# PowerAndUSB.net
KiCad netlist of a schematic drawn in Altium Designer
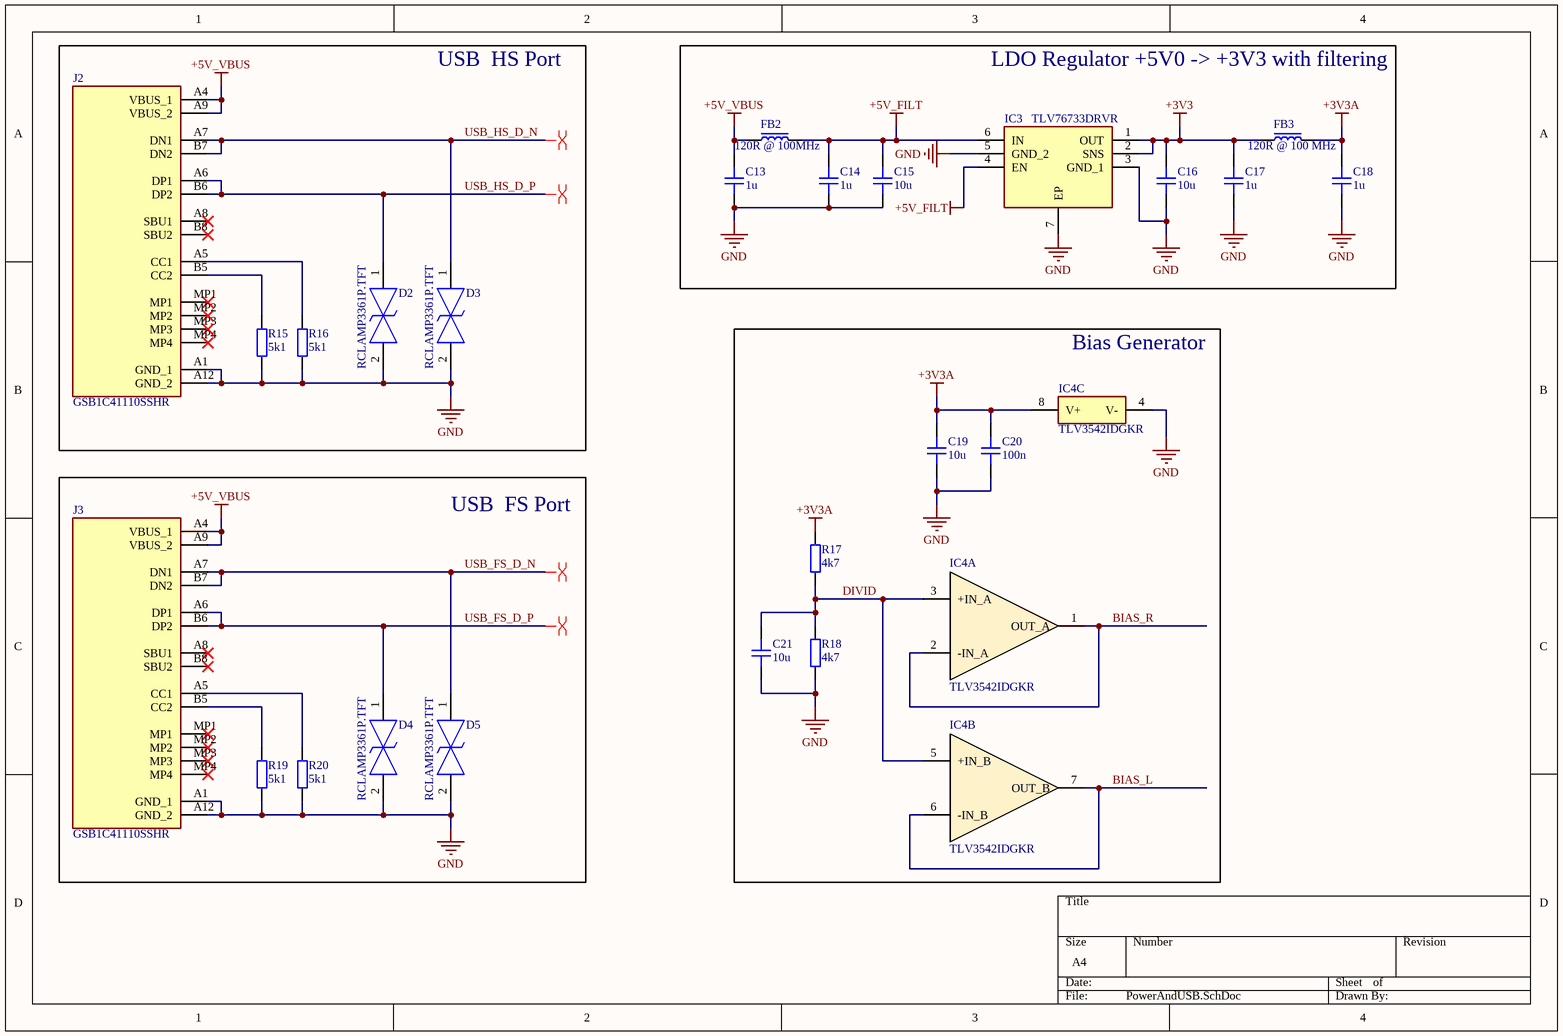
[diagram p0: PowerAndUSB.SchDoc]

(export (version "E")
  (design (tool "Eeschema 10.0.6"))
  (components
    (comp (ref "C13")
      (value "1u")
      (footprint "CAP_0805")
      (description "Capacitor SMD 0805")
      (libsource (lib "Schematic-Lib-PhilsLab") (part "CAP_0805"))
    )
    (comp (ref "C14")
      (value "1u")
      (footprint "CAP_0805")
      (description "Capacitor SMD 0805")
      (libsource (lib "Schematic-Lib-PhilsLab") (part "CAP_0805"))
    )
    (comp (ref "C15")
      (value "10u")
      (footprint "CAP_0805")
      (description "Capacitor SMD 0805")
      (libsource (lib "Schematic-Lib-PhilsLab") (part "CAP_0805"))
    )
    (comp (ref "C16")
      (value "10u")
      (footprint "CAP_0805")
      (description "Capacitor SMD 0805")
      (libsource (lib "Schematic-Lib-PhilsLab") (part "CAP_0805"))
    )
    (comp (ref "C17")
      (value "1u")
      (footprint "CAP_0402")
      (description "Capacitor SMD 0402")
      (libsource (lib "Schematic-Lib-PhilsLab") (part "CAP_0402"))
    )
    (comp (ref "C18")
      (value "1u")
      (footprint "CAP_0402")
      (description "Capacitor SMD 0402")
      (libsource (lib "Schematic-Lib-PhilsLab") (part "CAP_0402"))
    )
    (comp (ref "C19")
      (value "10u")
      (footprint "CAP_0603")
      (description "Capacitor SMD 0603")
      (libsource (lib "Schematic-Lib-PhilsLab") (part "CAP_0603"))
    )
    (comp (ref "C20")
      (value "100n")
      (footprint "CAP_0402")
      (description "Capacitor SMD 0402")
      (libsource (lib "Schematic-Lib-PhilsLab") (part "CAP_0402"))
    )
    (comp (ref "C21")
      (value "10u")
      (footprint "CAP_0603")
      (description "Capacitor SMD 0603")
      (libsource (lib "Schematic-Lib-PhilsLab") (part "CAP_0603"))
    )
    (comp (ref "D2")
      (value "RCLAMP3361P.TFT")
      (footprint "BAT_Detector_PCBLib:RCLAMP3361PTFT")
      (description "TVS Diode (Bi-directional)")
      (libsource (lib "BAT_Detector_SCHLib") (part "RCLAMP3361P.TFT"))
    )
    (comp (ref "D3")
      (value "RCLAMP3361P.TFT")
      (footprint "BAT_Detector_PCBLib:RCLAMP3361PTFT")
      (description "TVS Diode (Bi-directional)")
      (libsource (lib "BAT_Detector_SCHLib") (part "RCLAMP3361P.TFT"))
    )
    (comp (ref "D4")
      (value "RCLAMP3361P.TFT")
      (footprint "BAT_Detector_PCBLib:RCLAMP3361PTFT")
      (description "TVS Diode (Bi-directional)")
      (libsource (lib "BAT_Detector_SCHLib") (part "RCLAMP3361P.TFT"))
    )
    (comp (ref "D5")
      (value "RCLAMP3361P.TFT")
      (footprint "BAT_Detector_PCBLib:RCLAMP3361PTFT")
      (description "TVS Diode (Bi-directional)")
      (libsource (lib "BAT_Detector_SCHLib") (part "RCLAMP3361P.TFT"))
    )
    (comp (ref "FB2")
      (value "120R @ 100MHz")
      (footprint "FB_0805")
      (description "Ferrite Bead SMD 0805")
      (libsource (lib "Schematic-Lib-PhilsLab") (part "FB_0805"))
    )
    (comp (ref "FB3")
      (value "120R @ 100 MHz")
      (footprint "FB_0603")
      (description "Ferrite Bead SMD 0603")
      (libsource (lib "Schematic-Lib-PhilsLab") (part "FB_0603"))
    )
    (comp (ref "IC3")
      (value "TLV76733DRVR")
      (footprint "BAT_Detector_PCBLib:SON65P200X200X80-7N")
      (description "Integrated Circuit")
      (fields (field (name "MOUSER PART NUMBER") "595-TLV76733DRVR"))
      (libsource (lib "BAT_Detector_SCHLib") (part "TLV76733DRVR"))
    )
    (comp (ref "IC4")
      (value "TLV3542IDGKR")
      (footprint "BAT_Detector_PCBLib:SOP65P490X110-8N")
      (description "Integrated Circuit")
      (fields (field (name "MOUSER PART NUMBER") "595-TLV3542IDGKR"))
      (libsource (lib "BAT_Detector_SCHLib") (part "TLV3542IDGKR"))
    )
    (comp (ref "J2")
      (value "GSB1C41110SSHR")
      (footprint "BAT_Detector_PCBLib:GSB1C41110SSHR")
      (description "Connector")
      (libsource (lib "BAT_Detector_SCHLib") (part "GSB1C41110SSHR"))
    )
    (comp (ref "J3")
      (value "GSB1C41110SSHR")
      (footprint "BAT_Detector_PCBLib:GSB1C41110SSHR")
      (description "Connector")
      (libsource (lib "BAT_Detector_SCHLib") (part "GSB1C41110SSHR"))
    )
    (comp (ref "R15")
      (value "5k1")
      (footprint "RES_0402")
      (description "Resistor SMD 0402")
      (libsource (lib "Schematic-Lib-PhilsLab") (part "RES_0402"))
    )
    (comp (ref "R16")
      (value "5k1")
      (footprint "RES_0402")
      (description "Resistor SMD 0402")
      (libsource (lib "Schematic-Lib-PhilsLab") (part "RES_0402"))
    )
    (comp (ref "R17")
      (value "4k7")
      (footprint "RES_0603")
      (description "Resistor SMD 0603")
      (libsource (lib "Schematic-Lib-PhilsLab") (part "RES_0603"))
    )
    (comp (ref "R18")
      (value "4k7")
      (footprint "RES_0603")
      (description "Resistor SMD 0603")
      (libsource (lib "Schematic-Lib-PhilsLab") (part "RES_0603"))
    )
    (comp (ref "R19")
      (value "5k1")
      (footprint "RES_0402")
      (description "Resistor SMD 0402")
      (libsource (lib "Schematic-Lib-PhilsLab") (part "RES_0402"))
    )
    (comp (ref "R20")
      (value "5k1")
      (footprint "RES_0402")
      (description "Resistor SMD 0402")
      (libsource (lib "Schematic-Lib-PhilsLab") (part "RES_0402"))
    )
  )
  (nets
    (net (code "1") (name "+3V3") (class "Default")
      (node (ref "C16") (pin "2") (pinfunction "2_2") (pintype "passive"))
      (node (ref "C17") (pin "1") (pinfunction "1_1") (pintype "passive"))
      (node (ref "FB3") (pin "1") (pinfunction "1_1") (pintype "passive"))
      (node (ref "IC3") (pin "1") (pinfunction "OUT_1") (pintype "passive"))
      (node (ref "IC3") (pin "2") (pinfunction "SNS_2") (pintype "passive"))
    )
    (net (code "2") (name "+3V3A") (class "Default")
      (node (ref "C18") (pin "1") (pinfunction "1_1") (pintype "passive"))
      (node (ref "C19") (pin "2") (pinfunction "2_2") (pintype "passive"))
      (node (ref "C20") (pin "2") (pinfunction "2_2") (pintype "passive"))
      (node (ref "FB3") (pin "2") (pinfunction "2_2") (pintype "passive"))
      (node (ref "IC4") (pin "8") (pinfunction "V+_8") (pintype "passive"))
      (node (ref "R17") (pin "2") (pinfunction "2_2") (pintype "passive"))
    )
    (net (code "3") (name "+5V_FILT") (class "Default")
      (node (ref "C14") (pin "2") (pinfunction "2_2") (pintype "passive"))
      (node (ref "C15") (pin "2") (pinfunction "2_2") (pintype "passive"))
      (node (ref "FB2") (pin "2") (pinfunction "2_2") (pintype "passive"))
      (node (ref "IC3") (pin "4") (pinfunction "EN_4") (pintype "passive"))
      (node (ref "IC3") (pin "6") (pinfunction "IN_6") (pintype "passive"))
    )
    (net (code "4") (name "+5V_VBUS") (class "Default")
      (node (ref "C13") (pin "2") (pinfunction "2_2") (pintype "passive"))
      (node (ref "FB2") (pin "1") (pinfunction "1_1") (pintype "passive"))
      (node (ref "J2") (pin "A4") (pinfunction "VBUS_1_A4") (pintype "passive"))
      (node (ref "J2") (pin "A9") (pinfunction "VBUS_2_A9") (pintype "passive"))
      (node (ref "J3") (pin "A4") (pinfunction "VBUS_1_A4") (pintype "passive"))
      (node (ref "J3") (pin "A9") (pinfunction "VBUS_2_A9") (pintype "passive"))
    )
    (net (code "5") (name "/BIAS_L") (class "Default")
      (node (ref "IC4") (pin "6") (pinfunction "-IN_B_6") (pintype "passive"))
      (node (ref "IC4") (pin "7") (pinfunction "OUT_B_7") (pintype "passive"))
    )
    (net (code "6") (name "/BIAS_R") (class "Default")
      (node (ref "IC4") (pin "1") (pinfunction "OUT_A_1") (pintype "passive"))
      (node (ref "IC4") (pin "2") (pinfunction "-IN_A_2") (pintype "passive"))
    )
    (net (code "7") (name "/DIVID") (class "Default")
      (node (ref "C21") (pin "2") (pinfunction "2_2") (pintype "passive"))
      (node (ref "IC4") (pin "3") (pinfunction "+IN_A_3") (pintype "passive"))
      (node (ref "IC4") (pin "5") (pinfunction "+IN_B_5") (pintype "passive"))
      (node (ref "R17") (pin "1") (pinfunction "1_1") (pintype "passive"))
      (node (ref "R18") (pin "2") (pinfunction "2_2") (pintype "passive"))
    )
    (net (code "8") (name "/USB_FS_D_N") (class "Default")
      (node (ref "D5") (pin "1") (pinfunction "1_1") (pintype "passive"))
      (node (ref "J3") (pin "A7") (pinfunction "DN1_A7") (pintype "passive"))
      (node (ref "J3") (pin "B7") (pinfunction "DN2_B7") (pintype "passive"))
    )
    (net (code "9") (name "/USB_FS_D_P") (class "Default")
      (node (ref "D4") (pin "1") (pinfunction "1_1") (pintype "passive"))
      (node (ref "J3") (pin "A6") (pinfunction "DP1_A6") (pintype "passive"))
      (node (ref "J3") (pin "B6") (pinfunction "DP2_B6") (pintype "passive"))
    )
    (net (code "10") (name "/USB_HS_D_N") (class "Default")
      (node (ref "D3") (pin "1") (pinfunction "1_1") (pintype "passive"))
      (node (ref "J2") (pin "A7") (pinfunction "DN1_A7") (pintype "passive"))
      (node (ref "J2") (pin "B7") (pinfunction "DN2_B7") (pintype "passive"))
    )
    (net (code "11") (name "/USB_HS_D_P") (class "Default")
      (node (ref "D2") (pin "1") (pinfunction "1_1") (pintype "passive"))
      (node (ref "J2") (pin "A6") (pinfunction "DP1_A6") (pintype "passive"))
      (node (ref "J2") (pin "B6") (pinfunction "DP2_B6") (pintype "passive"))
    )
    (net (code "12") (name "GND") (class "Default")
      (node (ref "C13") (pin "1") (pinfunction "1_1") (pintype "passive"))
      (node (ref "C14") (pin "1") (pinfunction "1_1") (pintype "passive"))
      (node (ref "C15") (pin "1") (pinfunction "1_1") (pintype "passive"))
      (node (ref "C16") (pin "1") (pinfunction "1_1") (pintype "passive"))
      (node (ref "C17") (pin "2") (pinfunction "2_2") (pintype "passive"))
      (node (ref "C18") (pin "2") (pinfunction "2_2") (pintype "passive"))
      (node (ref "C19") (pin "1") (pinfunction "1_1") (pintype "passive"))
      (node (ref "C20") (pin "1") (pinfunction "1_1") (pintype "passive"))
      (node (ref "C21") (pin "1") (pinfunction "1_1") (pintype "passive"))
      (node (ref "D2") (pin "2") (pinfunction "2_2") (pintype "passive"))
      (node (ref "D3") (pin "2") (pinfunction "2_2") (pintype "passive"))
      (node (ref "D4") (pin "2") (pinfunction "2_2") (pintype "passive"))
      (node (ref "D5") (pin "2") (pinfunction "2_2") (pintype "passive"))
      (node (ref "IC3") (pin "3") (pinfunction "GND_1_3") (pintype "passive"))
      (node (ref "IC3") (pin "5") (pinfunction "GND_2_5") (pintype "passive"))
      (node (ref "IC3") (pin "7") (pinfunction "EP_7") (pintype "passive"))
      (node (ref "IC4") (pin "4") (pinfunction "V-_4") (pintype "passive"))
      (node (ref "J2") (pin "A1") (pinfunction "GND_1_A1") (pintype "passive"))
      (node (ref "J2") (pin "A12") (pinfunction "GND_2_A12") (pintype "passive"))
      (node (ref "J3") (pin "A1") (pinfunction "GND_1_A1") (pintype "passive"))
      (node (ref "J3") (pin "A12") (pinfunction "GND_2_A12") (pintype "passive"))
      (node (ref "R15") (pin "1") (pinfunction "1_1") (pintype "passive"))
      (node (ref "R16") (pin "1") (pinfunction "1_1") (pintype "passive"))
      (node (ref "R18") (pin "1") (pinfunction "1_1") (pintype "passive"))
      (node (ref "R19") (pin "1") (pinfunction "1_1") (pintype "passive"))
      (node (ref "R20") (pin "1") (pinfunction "1_1") (pintype "passive"))
    )
    (net (code "13") (name "Net-(J2-CC1)") (class "Default")
      (node (ref "J2") (pin "A5") (pinfunction "CC1_A5") (pintype "passive"))
      (node (ref "R16") (pin "2") (pinfunction "2_2") (pintype "passive"))
    )
    (net (code "14") (name "Net-(J2-CC2)") (class "Default")
      (node (ref "J2") (pin "B5") (pinfunction "CC2_B5") (pintype "passive"))
      (node (ref "R15") (pin "2") (pinfunction "2_2") (pintype "passive"))
    )
    (net (code "15") (name "Net-(J3-CC1)") (class "Default")
      (node (ref "J3") (pin "A5") (pinfunction "CC1_A5") (pintype "passive"))
      (node (ref "R20") (pin "2") (pinfunction "2_2") (pintype "passive"))
    )
    (net (code "16") (name "Net-(J3-CC2)") (class "Default")
      (node (ref "J3") (pin "B5") (pinfunction "CC2_B5") (pintype "passive"))
      (node (ref "R19") (pin "2") (pinfunction "2_2") (pintype "passive"))
    )
    (net (code "17") (name "unconnected-(J2-PadMP1)") (class "Default")
      (node (ref "J2") (pin "MP1") (pinfunction "MP1_MP1") (pintype "passive+no_connect"))
    )
    (net (code "18") (name "unconnected-(J2-PadMP2)") (class "Default")
      (node (ref "J2") (pin "MP2") (pinfunction "MP2_MP2") (pintype "passive+no_connect"))
    )
    (net (code "19") (name "unconnected-(J2-PadMP3)") (class "Default")
      (node (ref "J2") (pin "MP3") (pinfunction "MP3_MP3") (pintype "passive+no_connect"))
    )
    (net (code "20") (name "unconnected-(J2-PadMP4)") (class "Default")
      (node (ref "J2") (pin "MP4") (pinfunction "MP4_MP4") (pintype "passive+no_connect"))
    )
    (net (code "21") (name "unconnected-(J2-SBU1-PadA8)") (class "Default")
      (node (ref "J2") (pin "A8") (pinfunction "SBU1_A8") (pintype "passive+no_connect"))
    )
    (net (code "22") (name "unconnected-(J2-SBU2-PadB8)") (class "Default")
      (node (ref "J2") (pin "B8") (pinfunction "SBU2_B8") (pintype "passive+no_connect"))
    )
    (net (code "23") (name "unconnected-(J3-PadMP1)") (class "Default")
      (node (ref "J3") (pin "MP1") (pinfunction "MP1_MP1") (pintype "passive+no_connect"))
    )
    (net (code "24") (name "unconnected-(J3-PadMP2)") (class "Default")
      (node (ref "J3") (pin "MP2") (pinfunction "MP2_MP2") (pintype "passive+no_connect"))
    )
    (net (code "25") (name "unconnected-(J3-PadMP3)") (class "Default")
      (node (ref "J3") (pin "MP3") (pinfunction "MP3_MP3") (pintype "passive+no_connect"))
    )
    (net (code "26") (name "unconnected-(J3-PadMP4)") (class "Default")
      (node (ref "J3") (pin "MP4") (pinfunction "MP4_MP4") (pintype "passive+no_connect"))
    )
    (net (code "27") (name "unconnected-(J3-SBU1-PadA8)") (class "Default")
      (node (ref "J3") (pin "A8") (pinfunction "SBU1_A8") (pintype "passive+no_connect"))
    )
    (net (code "28") (name "unconnected-(J3-SBU2-PadB8)") (class "Default")
      (node (ref "J3") (pin "B8") (pinfunction "SBU2_B8") (pintype "passive+no_connect"))
    )
  )
)
